# TPS40200BuckDesign.net
KiCad netlist of a schematic drawn in Altium Designer
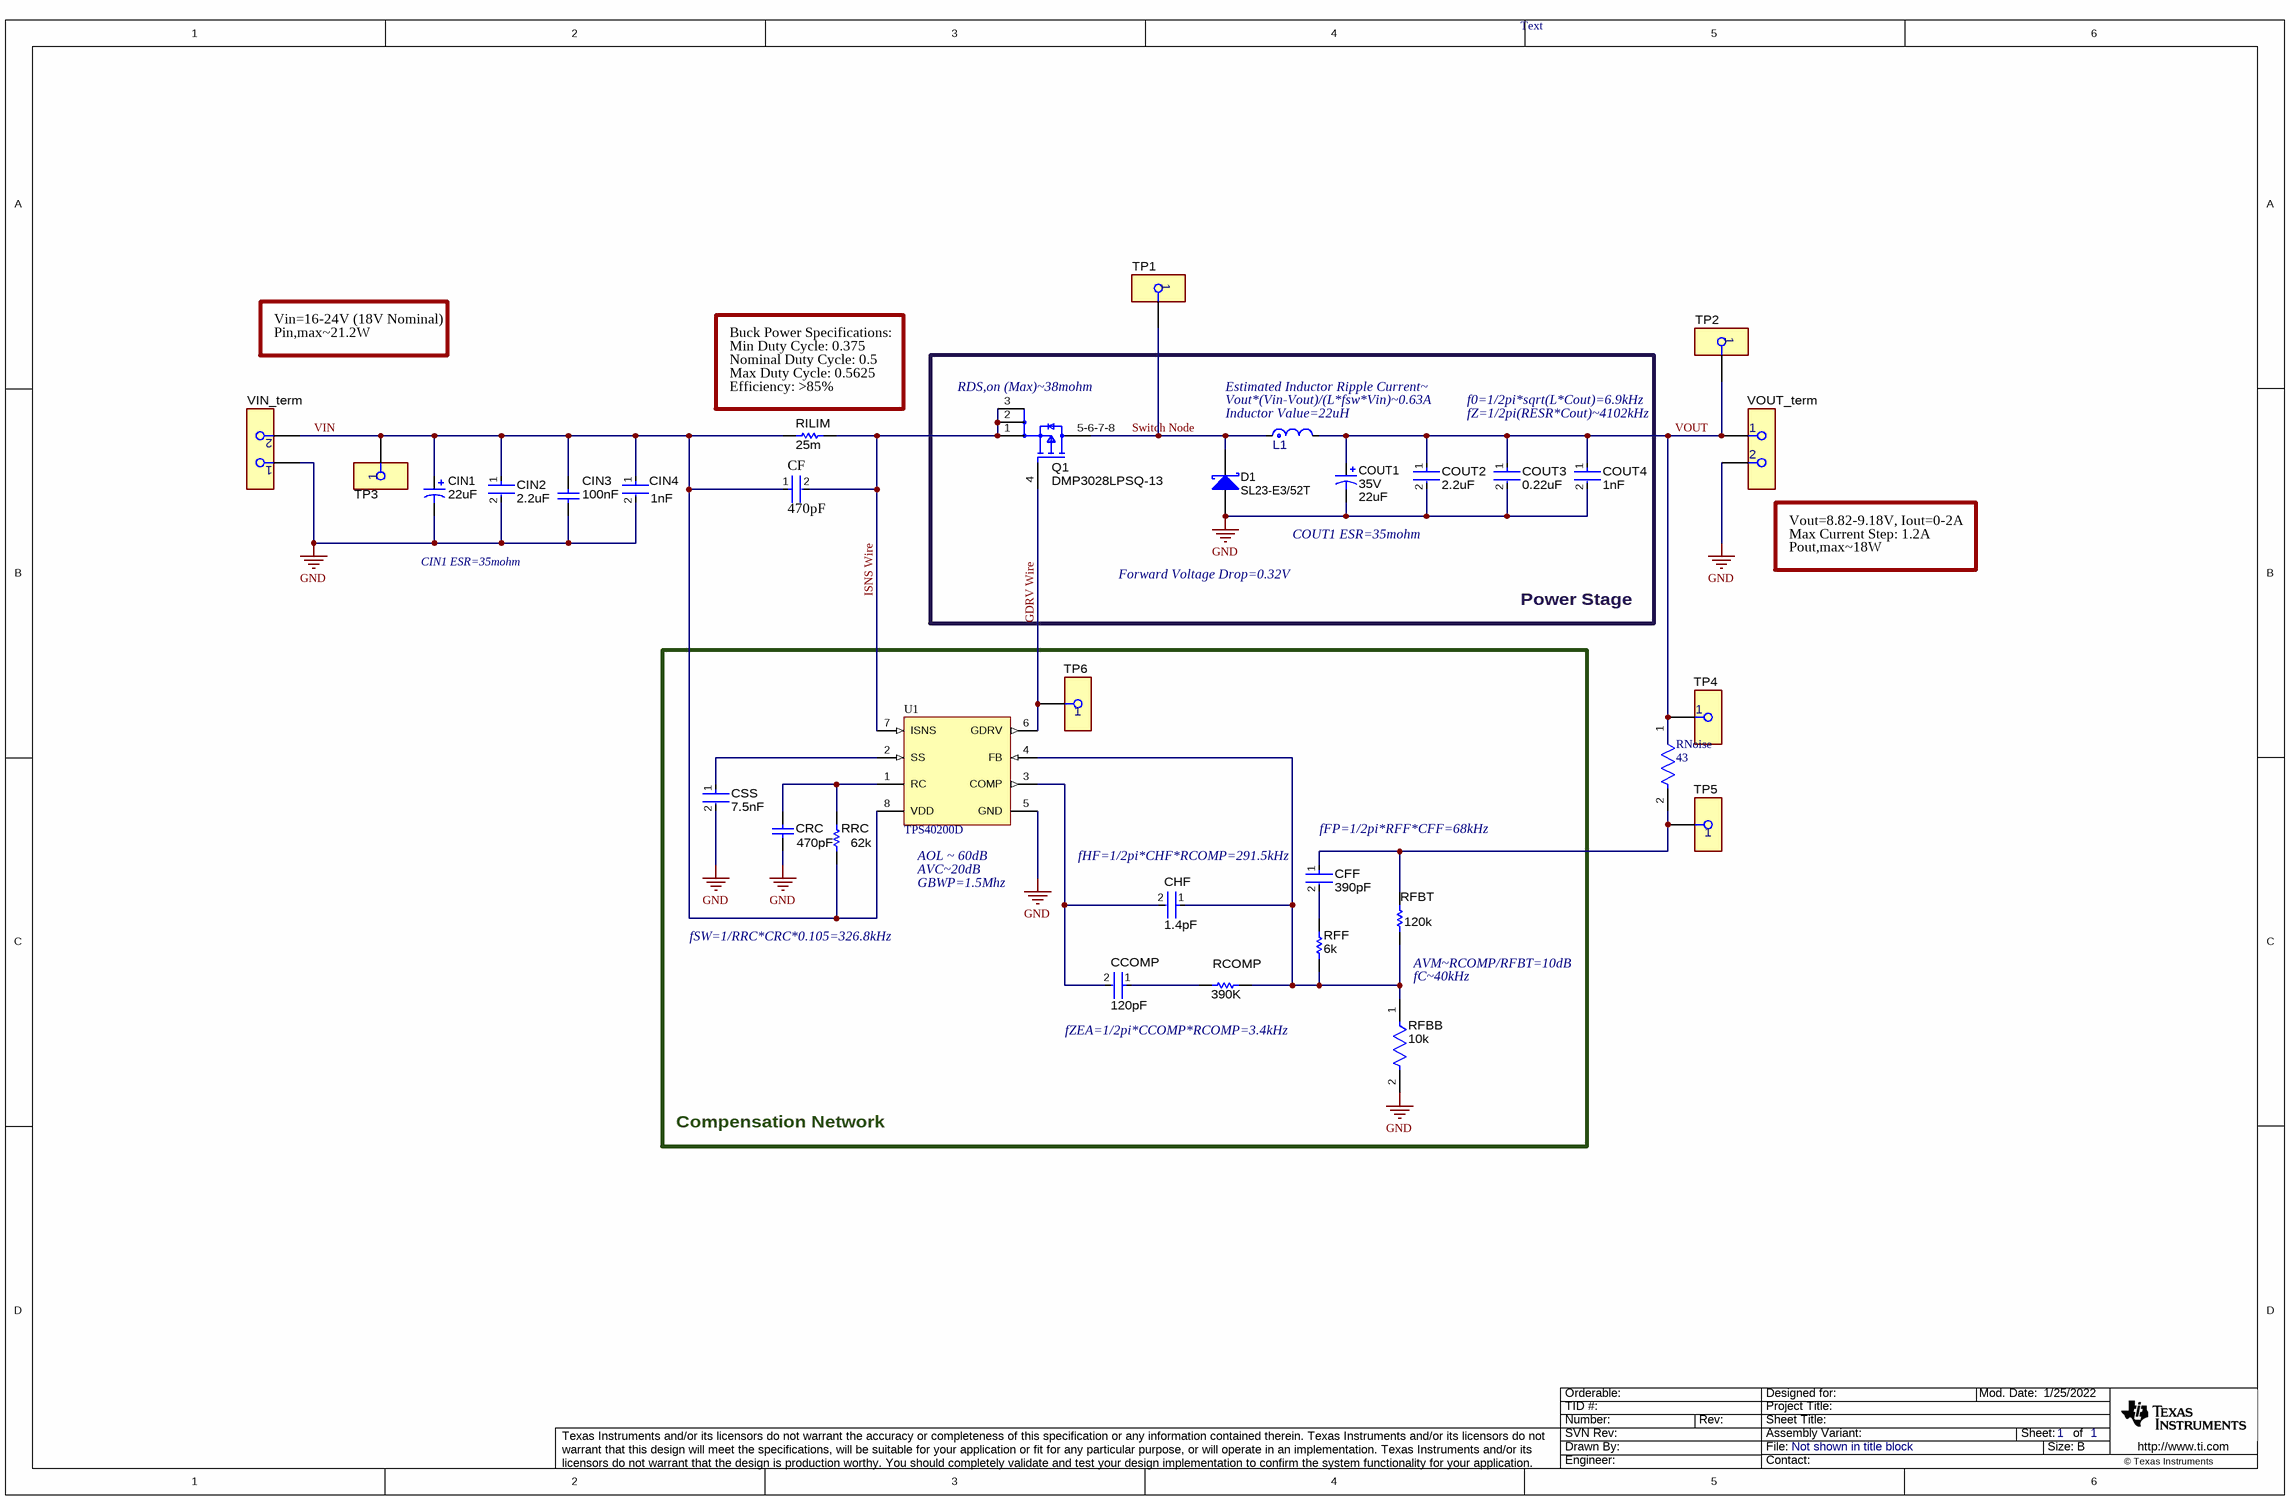
[diagram p0: TPS40200BuckDesign.SchDoc]

(export (version "E")
  (design (tool "Eeschema 10.0.6"))
  (components
    (comp (ref "CCOMP")
      (value "120pF")
      (footprint "FP-CL21-IPC_C")
      (description "CL21 Series 0805 120pF 200V ±5% Tolerance C0G Multilayer Ceramic Chip Capacitor")
      (fields (field (name "TOLERANCE") "5%"))
      (libsource (lib "Altium Content Vault") (part "b4654b650e69147ec39a6b967a45e02"))
    )
    (comp (ref "CF")
      (value "470pF")
      (footprint "FP-0805-L_2_01_0_2-W_1_25-IPC_B")
      (description "General Purpose Ceramic Capacitor, 0805, 470pF, 5%, C0G, 30ppm/°C, 100V")
      (fields (field (name "TOLERANCE") "5%") (field (name "VOLTAGE") "100V"))
      (libsource (lib "Altium Content Vault") (part "02cd4be3c70576c341d710602a673aa"))
    )
    (comp (ref "CFF")
      (value "390pF")
      (footprint "FP-CC0603-DA-MFG")
      (description "CAP CER 390PF 50V X7R 0603")
      (fields
        (field (name "OCTOPART") "https://octopart.com/cc0603krx7r9bb391-yageo-39467837")
        (field (name "MANUFACTURER") "YAGEO")
      )
      (libsource (lib "Altium Content Vault") (part "11868f565c42a9108669ba33697ecf6"))
    )
    (comp (ref "CHF")
      (value "1.4pF")
      (footprint "FP-CBR06C-MFG")
      (description "CBR0603 1.4 pF C0G 30ppm/°C 0.1 pF 50 V")
      (fields (field (name "MANUFACTURER PART NUMBER") "CBR06C149B5GAC") (field (name "TOLERANCE") "0.1 pF"))
      (libsource (lib "Altium Content Vault") (part "11868f565c42a9108669ba33697ecf6"))
    )
    (comp (ref "CIN1")
      (value "35SVPF22M")
      (footprint "CAPSMT_62_F61")
      (description "CAP, Aluminum Polymer, 22 uF, 35 V, +/- 20%, 0.035 ohm, F61 SMD")
      (fields
        (field (name "MANUFACTURER") "Panasonic")
        (field (name "VALUEDISPLAYED") "22uF")
        (field (name "PUBLISHER") "Texas Instruments")
      )
      (libsource (lib "Altium Vault - TI") (part "Cap_Polarized"))
    )
    (comp (ref "CIN2")
      (value "2.2uF")
      (footprint "FP-GRM188-0_1-e0_2_0_5-IPC_C")
      (description "Chip Multilayer Ceramic Capacitors for General Purpose, 0603, 2.2uF, X5R, 15%, 10%, 35V")
      (fields (field (name "VOLTAGE") "35V") (field (name "TOLERANCE") "10%"))
      (libsource (lib "Altium Content Vault") (part "11868f565c42a9108669ba33697ecf6"))
    )
    (comp (ref "CIN3")
      (value "100nF")
      (footprint "CAPC1608X90X40LL10T20")
      (fields (field (name "TOLERANCE") "-20%,+80%") (field (name "MANUFACTURER") "Yageo"))
      (libsource (lib "Altium Content Vault") (part "CAP-NP-2"))
    )
    (comp (ref "CIN4")
      (value "1nF")
      (footprint "FP-C0603C-CF-MFG")
      (description "CAP CER 1000PF 50V X7R 0603")
      (fields (field (name "TOLERANCE") "0.1") (field (name "MANUFACTURER PART NUMBER") "C0603C102K5RACTU"))
      (libsource (lib "Altium Content Vault") (part "b4654b650e69147ec39a6b967a45e02"))
    )
    (comp (ref "COUT1")
      (value "35SVPF22M")
      (footprint "CAPSMT_62_F61")
      (description "CAP, Aluminum Polymer, 22 uF, 35 V, +/- 20%, 0.035 ohm, F61 SMD")
      (fields
        (field (name "MANUFACTURER") "Panasonic")
        (field (name "VDC_V") "35V")
        (field (name "VALUEDISPLAYED") "22uF")
        (field (name "PUBLISHER") "Texas Instruments")
      )
      (libsource (lib "Altium Vault - TI") (part "Cap_Polarized"))
    )
    (comp (ref "COUT2")
      (value "2.2uF")
      (footprint "FP-CL10-IPC_C")
      (description "Cap Ceramic 2.2uF 10V Y5V -20/+80% Pad SMD 0603 +85°C T/R")
      (fields (field (name "TOLERANCE") "80%"))
      (libsource (lib "Altium Content Vault") (part "b4654b650e69147ec39a6b967a45e02"))
    )
    (comp (ref "COUT3")
      (value "0.22uF")
      (footprint "FP-GRM188-0_1-e0_2_0_5-IPC_C")
      (description "Chip Multilayer Ceramic Capacitors for General Purpose, 0603, 0.22uF, X7R, 15%, 10%, 50V")
      (fields (field (name "TOLERANCE") "10%"))
      (libsource (lib "Altium Content Vault") (part "11868f565c42a9108669ba33697ecf6"))
    )
    (comp (ref "COUT4")
      (value "1nF")
      (footprint "FP-CL10-IPC_C")
      (description "Cap Ceramic 1nF 100V X7R ±10% Pad SMD 0603 +125°C T/R")
      (fields (field (name "TOLERANCE") "10%") (field (name "VOLTAGE") "100V"))
      (libsource (lib "Altium Content Vault") (part "b4654b650e69147ec39a6b967a45e02"))
    )
    (comp (ref "CRC")
      (value "GCM1885C1H471JA16D")
      (footprint "0603")
      (description "CAP, CERM, 470 pF, 50 V, +/- 5%, C0G/NP0, AEC-Q200 Grade 1, 0603")
      (fields
        (field (name "MANUFACTURER") "MuRata")
        (field (name "VALUEDISPLAYED") "470pF")
        (field (name "PUBLISHER") "Texas Instruments")
      )
      (libsource (lib "Altium Vault - TI") (part "Capacitor"))
    )
    (comp (ref "CSS")
      (value "7.5nF")
      (footprint "FP-GRM188-0_1-e0_2_0_5-IPC_C")
      (description "Chip Multilayer Ceramic Capacitors for General Purpose, 0603, 7500pF, C0G, 30ppm/°C, 5%, 50V")
      (fields (field (name "TOLERANCE") "5%"))
      (libsource (lib "Altium Content Vault") (part "11868f565c42a9108669ba33697ecf6"))
    )
    (comp (ref "D1")
      (value "SL23-E3/52T")
      (footprint "SMB")
      (description "Diode, Schottky, 30 V, 2 A, SMB")
      (fields (field (name "MANUFACTURER") "Vishay-Semiconductor"))
      (libsource (lib "Altium Vault - TI") (part "DIODE_SCHOTTKY"))
    )
    (comp (ref "L1")
      (value "XAL8080-223MED")
      (footprint "FP-XAL8080-223MED_SMT_IND_8MM1_8MM6-MFG")
      (description "22 µH Shielded Molded Inductor 7.6A 32.9mOhm Max Nonstandard")
      (fields
        (field (name "MANUFACTURER") "Coilcraft")
        (field (name "MOUSER PART NUMBER") "994-XAL8080-223MED")
      )
      (libsource (lib "Altium Vault - TI") (part "SYM-XAL8080-223MED"))
    )
    (comp (ref "Q1")
      (value "DMP3028LPSQ-13")
      (footprint "FP-DMP3028LPSQ-13_PowerDI5060-8-MFG")
      (description "P-Channel 30 V 21A (Tc) 1.28W Surface Mount PowerDI5060-8")
      (fields
        (field (name "MANUFACTURER") "Diodes Inc.")
        (field (name "DIGIKEY PART NUMBER") "DMP3028LPSQ-13DICT-ND")
      )
      (libsource (lib "Altium Vault - TI") (part "SYM-DMP3028LPSQ-13"))
    )
    (comp (ref "RCOMP")
      (value "390K")
      (footprint "RESC0805(2012)_M")
      (description "390K 0.125W 5% 0805 (2012 Metric)  SMD")
      (fields (field (name "TOLERANCE") "5 %") (field (name "POWER") "0.125 W"))
      (libsource (lib "Altium Content Vault") (part "RES"))
    )
    (comp (ref "RFBB")
      (value "10k")
      (footprint "FP-MCT0603-IPC_B")
      (description "RES SMD 100 OHM 1% 1/8W 0603")
      (fields (field (name "TOLERANCE") "0.1%"))
      (libsource (lib "Altium Content Vault") (part "1029c3af85768c4190bb7ad29bc67b5"))
    )
    (comp (ref "RFBT")
      (value "120k")
      (footprint "RESC1609X50X30ML10T20")
      (fields (field (name "MANUFACTURER") "Vishay Dale") (field (name "PART NUMBER") "CRCW0603120KJNEA"))
      (libsource (lib "Altium Content Vault") (part "RES"))
    )
    (comp (ref "RFF")
      (value "6k")
      (footprint "RESC1608X55X25ML10T15")
      (fields (field (name "PART NUMBER") "RC0603JR-076K2L") (field (name "MANUFACTURER") "Yageo"))
      (libsource (lib "Altium Content Vault") (part "RES"))
    )
    (comp (ref "RILIM")
      (value "25m")
      (footprint "RESC2013X50X40ML20T20")
      (fields (field (name "MANUFACTURER") "Susumu") (field (name "PART NUMBER") "RL1220T-R025-J"))
      (libsource (lib "Altium Content Vault") (part "RES"))
    )
    (comp (ref "RNoise")
      (value "43")
      (footprint "FP-CR0603-IPC_C")
      (description "Thick Film Chip Resistors 0603 43Ω 0.1W 1% 100ppm/°C")
      (fields (field (name "TOLERANCE") "1%"))
      (libsource (lib "Altium Content Vault") (part "1029c3af85768c4190bb7ad29bc67b5"))
    )
    (comp (ref "RRC")
      (value "62k")
      (footprint "RESC1609X50X30NL10T20")
      (fields (field (name "MANUFACTURER") "Vishay Dale") (field (name "PART NUMBER") "CRCW060362K0FKEA"))
      (libsource (lib "Altium Content Vault") (part "RES"))
    )
    (comp (ref "TP1")
      (value "~")
      (footprint "FP-RCWCTE_SMT_TP-MFG")
      (description "PC Test Point Plating Surface Mount Mounting Type")
      (fields (field (name "MANUFACTURER") "KOA Speer") (field (name "PARTNUMBER") "RCWCTE"))
      (libsource (lib "") (part "SYM-RCWCTE_1"))
    )
    (comp (ref "TP2")
      (value "~")
      (footprint "FP-RCWCTE_SMT_TP-MFG")
      (description "PC Test Point Plating Surface Mount Mounting Type")
      (fields (field (name "MANUFACTURER") "KOA Speer") (field (name "PARTNUMBER") "RCWCTE"))
      (libsource (lib "") (part "SYM-RCWCTE_1"))
    )
    (comp (ref "TP3")
      (value "~")
      (footprint "FP-RCWCTE_SMT_TP-MFG")
      (description "PC Test Point Plating Surface Mount Mounting Type")
      (fields (field (name "MANUFACTURER") "KOA Speer") (field (name "PARTNUMBER") "RCWCTE"))
      (libsource (lib "") (part "SYM-RCWCTE_2"))
    )
    (comp (ref "TP4")
      (value "~")
      (footprint "FP-RCWCTE_SMT_TP-MFG")
      (description "PC Test Point Plating Surface Mount Mounting Type")
      (fields (field (name "MANUFACTURER") "KOA Speer") (field (name "PARTNUMBER") "RCWCTE"))
      (libsource (lib "") (part "SYM-RCWCTE_1"))
    )
    (comp (ref "TP5")
      (value "~")
      (footprint "FP-RCWCTE_SMT_TP-MFG")
      (description "PC Test Point Plating Surface Mount Mounting Type")
      (fields (field (name "MANUFACTURER") "KOA Speer") (field (name "PARTNUMBER") "RCWCTE"))
      (libsource (lib "Altium Vault - TI") (part "SYM-RCWCTE"))
    )
    (comp (ref "TP6")
      (value "~")
      (footprint "FP-RCWCTE_SMT_TP-MFG")
      (description "PC Test Point Plating Surface Mount Mounting Type")
      (fields (field (name "MANUFACTURER") "KOA Speer") (field (name "PARTNUMBER") "RCWCTE"))
      (libsource (lib "Altium Vault - TI") (part "SYM-RCWCTE"))
    )
    (comp (ref "U1")
      (value "TPS40200D")
      (footprint "D0008A_N")
      (fields (field (name "MANUFACTURER") "Texas Instruments"))
      (libsource (lib "Altium Content Vault") (part "TI-TPS40200D8"))
    )
    (comp (ref "VIN_term")
      (value "~")
      (footprint "FP-691137710002_HDR2-MFG")
      (description "TERM BLK 2POS SIDE ENTRY 5MM PCB")
      (fields (field (name "PARTNUMBER") "691137710002") (field (name "MANUFACTURER") "Würth Elektronik"))
      (libsource (lib "") (part "SYM-1720033_1"))
    )
    (comp (ref "VOUT_term")
      (value "~")
      (footprint "FP-691137710002_HDR2-MFG")
      (description "TERM BLK 2POS SIDE ENTRY 5MM PCB")
      (fields (field (name "PARTNUMBER") "691137710002") (field (name "MANUFACTURER") "Würth Elektronik"))
      (libsource (lib "Altium Vault - TI") (part "SYM-1720033"))
    )
  )
  (nets
    (net (code "1") (name "/GDRV Wire") (class "Default")
      (node (ref "Q1") (pin "4") (pinfunction "G_4") (pintype "passive"))
      (node (ref "TP6") (pin "1") (pinfunction "1_1") (pintype "passive"))
      (node (ref "U1") (pin "6") (pinfunction "GDRV_6") (pintype "output"))
    )
    (net (code "2") (name "/ISNS Wire") (class "Default")
      (node (ref "CF") (pin "2") (pinfunction "2_2") (pintype "passive"))
      (node (ref "Q1") (pin "1") (pinfunction "S_1") (pintype "passive"))
      (node (ref "Q1") (pin "2") (pinfunction "S_2") (pintype "passive"))
      (node (ref "Q1") (pin "3") (pinfunction "S_3") (pintype "passive"))
      (node (ref "RILIM") (pin "2") (pinfunction "2_2") (pintype "passive"))
      (node (ref "U1") (pin "7") (pinfunction "ISNS_7") (pintype "input"))
    )
    (net (code "3") (name "/Switch Node") (class "Default")
      (node (ref "D1") (pin "1") (pinfunction "K_1") (pintype "passive"))
      (node (ref "L1") (pin "1") (pinfunction "1_1") (pintype "passive"))
      (node (ref "Q1") (pin "5-6-7-8") (pinfunction "D_5-6-7-8") (pintype "passive"))
      (node (ref "TP1") (pin "1") (pinfunction "1_1") (pintype "passive"))
    )
    (net (code "4") (name "/VIN") (class "Default")
      (node (ref "CF") (pin "1") (pinfunction "1_1") (pintype "passive"))
      (node (ref "CIN1") (pin "1") (pinfunction "+_1") (pintype "passive"))
      (node (ref "CIN2") (pin "1") (pinfunction "1_1") (pintype "passive"))
      (node (ref "CIN3") (pin "2") (pinfunction "2_2") (pintype "passive"))
      (node (ref "CIN4") (pin "1") (pinfunction "1_1") (pintype "passive"))
      (node (ref "RILIM") (pin "1") (pinfunction "1_1") (pintype "passive"))
      (node (ref "RRC") (pin "1") (pinfunction "1_1") (pintype "passive"))
      (node (ref "TP3") (pin "1") (pinfunction "1_1") (pintype "passive"))
      (node (ref "U1") (pin "8") (pinfunction "VDD_8") (pintype "power_in"))
      (node (ref "VIN_term") (pin "2") (pinfunction "2_2") (pintype "passive"))
    )
    (net (code "5") (name "/VOUT") (class "Default")
      (node (ref "COUT1") (pin "1") (pinfunction "+_1") (pintype "passive"))
      (node (ref "COUT2") (pin "1") (pinfunction "1_1") (pintype "passive"))
      (node (ref "COUT3") (pin "1") (pinfunction "1_1") (pintype "passive"))
      (node (ref "COUT4") (pin "1") (pinfunction "1_1") (pintype "passive"))
      (node (ref "L1") (pin "2") (pinfunction "2_2") (pintype "passive"))
      (node (ref "RNoise") (pin "1") (pinfunction "1_1") (pintype "passive"))
      (node (ref "TP2") (pin "1") (pinfunction "1_1") (pintype "passive"))
      (node (ref "TP4") (pin "1") (pinfunction "1_1") (pintype "passive"))
      (node (ref "VOUT_term") (pin "1") (pinfunction "1_1") (pintype "passive"))
    )
    (net (code "6") (name "GND") (class "Default")
      (node (ref "CIN1") (pin "2") (pinfunction "-_2") (pintype "passive"))
      (node (ref "CIN2") (pin "2") (pinfunction "2_2") (pintype "passive"))
      (node (ref "CIN3") (pin "1") (pinfunction "1_1") (pintype "passive"))
      (node (ref "CIN4") (pin "2") (pinfunction "2_2") (pintype "passive"))
      (node (ref "COUT1") (pin "2") (pinfunction "-_2") (pintype "passive"))
      (node (ref "COUT2") (pin "2") (pinfunction "2_2") (pintype "passive"))
      (node (ref "COUT3") (pin "2") (pinfunction "2_2") (pintype "passive"))
      (node (ref "COUT4") (pin "2") (pinfunction "2_2") (pintype "passive"))
      (node (ref "CRC") (pin "2") (pinfunction "2_2") (pintype "passive"))
      (node (ref "CSS") (pin "2") (pinfunction "2_2") (pintype "passive"))
      (node (ref "D1") (pin "2") (pinfunction "A_2") (pintype "passive"))
      (node (ref "RFBB") (pin "2") (pinfunction "2_2") (pintype "passive"))
      (node (ref "U1") (pin "5") (pinfunction "GND_5") (pintype "power_in"))
      (node (ref "VIN_term") (pin "1") (pinfunction "1_1") (pintype "passive"))
      (node (ref "VOUT_term") (pin "2") (pinfunction "2_2") (pintype "passive"))
    )
    (net (code "7") (name "Net-(CCOMP-Pad1)") (class "Default")
      (node (ref "CCOMP") (pin "1") (pinfunction "1_1") (pintype "passive"))
      (node (ref "RCOMP") (pin "1") (pinfunction "1_1") (pintype "passive"))
    )
    (net (code "8") (name "Net-(CFF-Pad1)") (class "Default")
      (node (ref "CFF") (pin "1") (pinfunction "1_1") (pintype "passive"))
      (node (ref "RFBT") (pin "2") (pinfunction "2_2") (pintype "passive"))
      (node (ref "RNoise") (pin "2") (pinfunction "2_2") (pintype "passive"))
      (node (ref "TP5") (pin "1") (pinfunction "1_1") (pintype "passive"))
    )
    (net (code "9") (name "Net-(CFF-Pad2)") (class "Default")
      (node (ref "CFF") (pin "2") (pinfunction "2_2") (pintype "passive"))
      (node (ref "RFF") (pin "2") (pinfunction "2_2") (pintype "passive"))
    )
    (net (code "10") (name "Net-(U1-COMP)") (class "Default")
      (node (ref "CCOMP") (pin "2") (pinfunction "2_2") (pintype "passive"))
      (node (ref "CHF") (pin "2") (pinfunction "2_2") (pintype "passive"))
      (node (ref "U1") (pin "3") (pinfunction "COMP_3") (pintype "output"))
    )
    (net (code "11") (name "Net-(U1-FB)") (class "Default")
      (node (ref "CHF") (pin "1") (pinfunction "1_1") (pintype "passive"))
      (node (ref "RCOMP") (pin "2") (pinfunction "2_2") (pintype "passive"))
      (node (ref "RFBB") (pin "1") (pinfunction "1_1") (pintype "passive"))
      (node (ref "RFBT") (pin "1") (pinfunction "1_1") (pintype "passive"))
      (node (ref "RFF") (pin "1") (pinfunction "1_1") (pintype "passive"))
      (node (ref "U1") (pin "4") (pinfunction "FB_4") (pintype "input"))
    )
    (net (code "12") (name "Net-(U1-RC)") (class "Default")
      (node (ref "CRC") (pin "1") (pinfunction "1_1") (pintype "passive"))
      (node (ref "RRC") (pin "2") (pinfunction "2_2") (pintype "passive"))
      (node (ref "U1") (pin "1") (pinfunction "RC_1") (pintype "passive"))
    )
    (net (code "13") (name "Net-(U1-SS)") (class "Default")
      (node (ref "CSS") (pin "1") (pinfunction "1_1") (pintype "passive"))
      (node (ref "U1") (pin "2") (pinfunction "SS_2") (pintype "input"))
    )
  )
)
